# Sheet1.net
KiCad netlist of a schematic drawn in Altium Designer
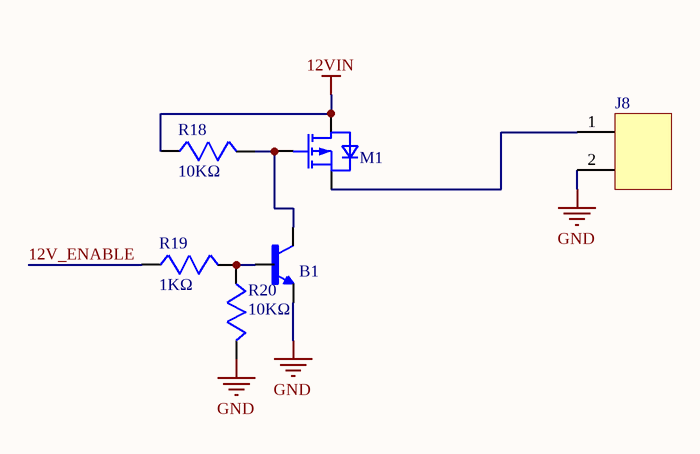
[diagram p0: Sheet1.SchDoc]

(export (version "E")
  (design (tool "Eeschema 10.0.6"))
  (components
    (comp (ref "B1")
      (value "MMBT3904")
      (footprint "MMBT3904 RFG")
      (description "TRANS NPN 40V 0.2A SOT23-3")
      (libsource (lib "Schlib1") (part "MMBT3904"))
    )
    (comp (ref "J8")
      (value "2 POS")
      (footprint "0901362102")
      (description "CONN HEADER R/A 2POS 2.54MM")
      (fields (field (name "MPN") "0901362102"))
      (libsource (lib "Schlib1") (part "0901362102"))
    )
    (comp (ref "M1")
      (value "mosfet")
      (footprint "IRLML6402")
      (description "MOSFET N-CH 12V 2.1A 3PICOSTAR")
      (fields (field (name "MPN") "IRLML6402"))
      (libsource (lib "Schlib1") (part "IRLML6402"))
    )
    (comp (ref "R18")
      (value "10KΩ")
      (footprint "402 RESISTOR")
      (description "RES SMD 0402")
      (fields (field (name "MPN") "RNCF0402BTE10K0") (field (name "Comment") "0402. RESİSTOR"))
      (libsource (lib "Schlib1") (part "RES SMD 0402"))
    )
    (comp (ref "R19")
      (value "1KΩ")
      (footprint "402 RESISTOR")
      (description "RES SMD 0402")
      (fields (field (name "MPN") "CR0402FC1KS001") (field (name "Comment") "0402. RESİSTOR"))
      (libsource (lib "Schlib1") (part "RES SMD 0402"))
    )
    (comp (ref "R20")
      (value "10KΩ")
      (footprint "402 RESISTOR")
      (description "RES SMD 0402")
      (fields (field (name "MPN") "RNCF0402BTE10K0") (field (name "Comment") "0402. RESİSTOR"))
      (libsource (lib "Schlib1") (part "RES SMD 0402"))
    )
  )
  (nets
    (net (code "1") (name "/12V_ENABLE") (class "Default") (node (ref "R19") (pin "1") (pintype "passive")))
    (net (code "2") (name "12VIN") (class "Default")
      (node (ref "M1") (pin "3") (pinfunction "DRAIN_3") (pintype "passive"))
      (node (ref "R18") (pin "1") (pintype "passive"))
    )
    (net (code "3") (name "GND") (class "Default")
      (node (ref "B1") (pin "2") (pinfunction "E_2") (pintype "passive"))
      (node (ref "J8") (pin "2") (pintype "passive"))
      (node (ref "R20") (pin "2") (pintype "passive"))
    )
    (net (code "4") (name "Net-(B1-B)") (class "Default")
      (node (ref "B1") (pin "1") (pinfunction "B_1") (pintype "passive"))
      (node (ref "R19") (pin "2") (pintype "passive"))
      (node (ref "R20") (pin "1") (pintype "passive"))
    )
    (net (code "5") (name "Net-(B1-C)") (class "Default")
      (node (ref "B1") (pin "3") (pinfunction "C_3") (pintype "passive"))
      (node (ref "M1") (pin "1") (pinfunction "GATE_1") (pintype "passive"))
      (node (ref "R18") (pin "2") (pintype "passive"))
    )
    (net (code "6") (name "Net-(M1-SOURCE)") (class "Default")
      (node (ref "J8") (pin "1") (pintype "passive"))
      (node (ref "M1") (pin "2") (pinfunction "SOURCE_2") (pintype "passive"))
    )
  )
)
